# motherboard.net
KiCad netlist of a schematic drawn in EAGLE
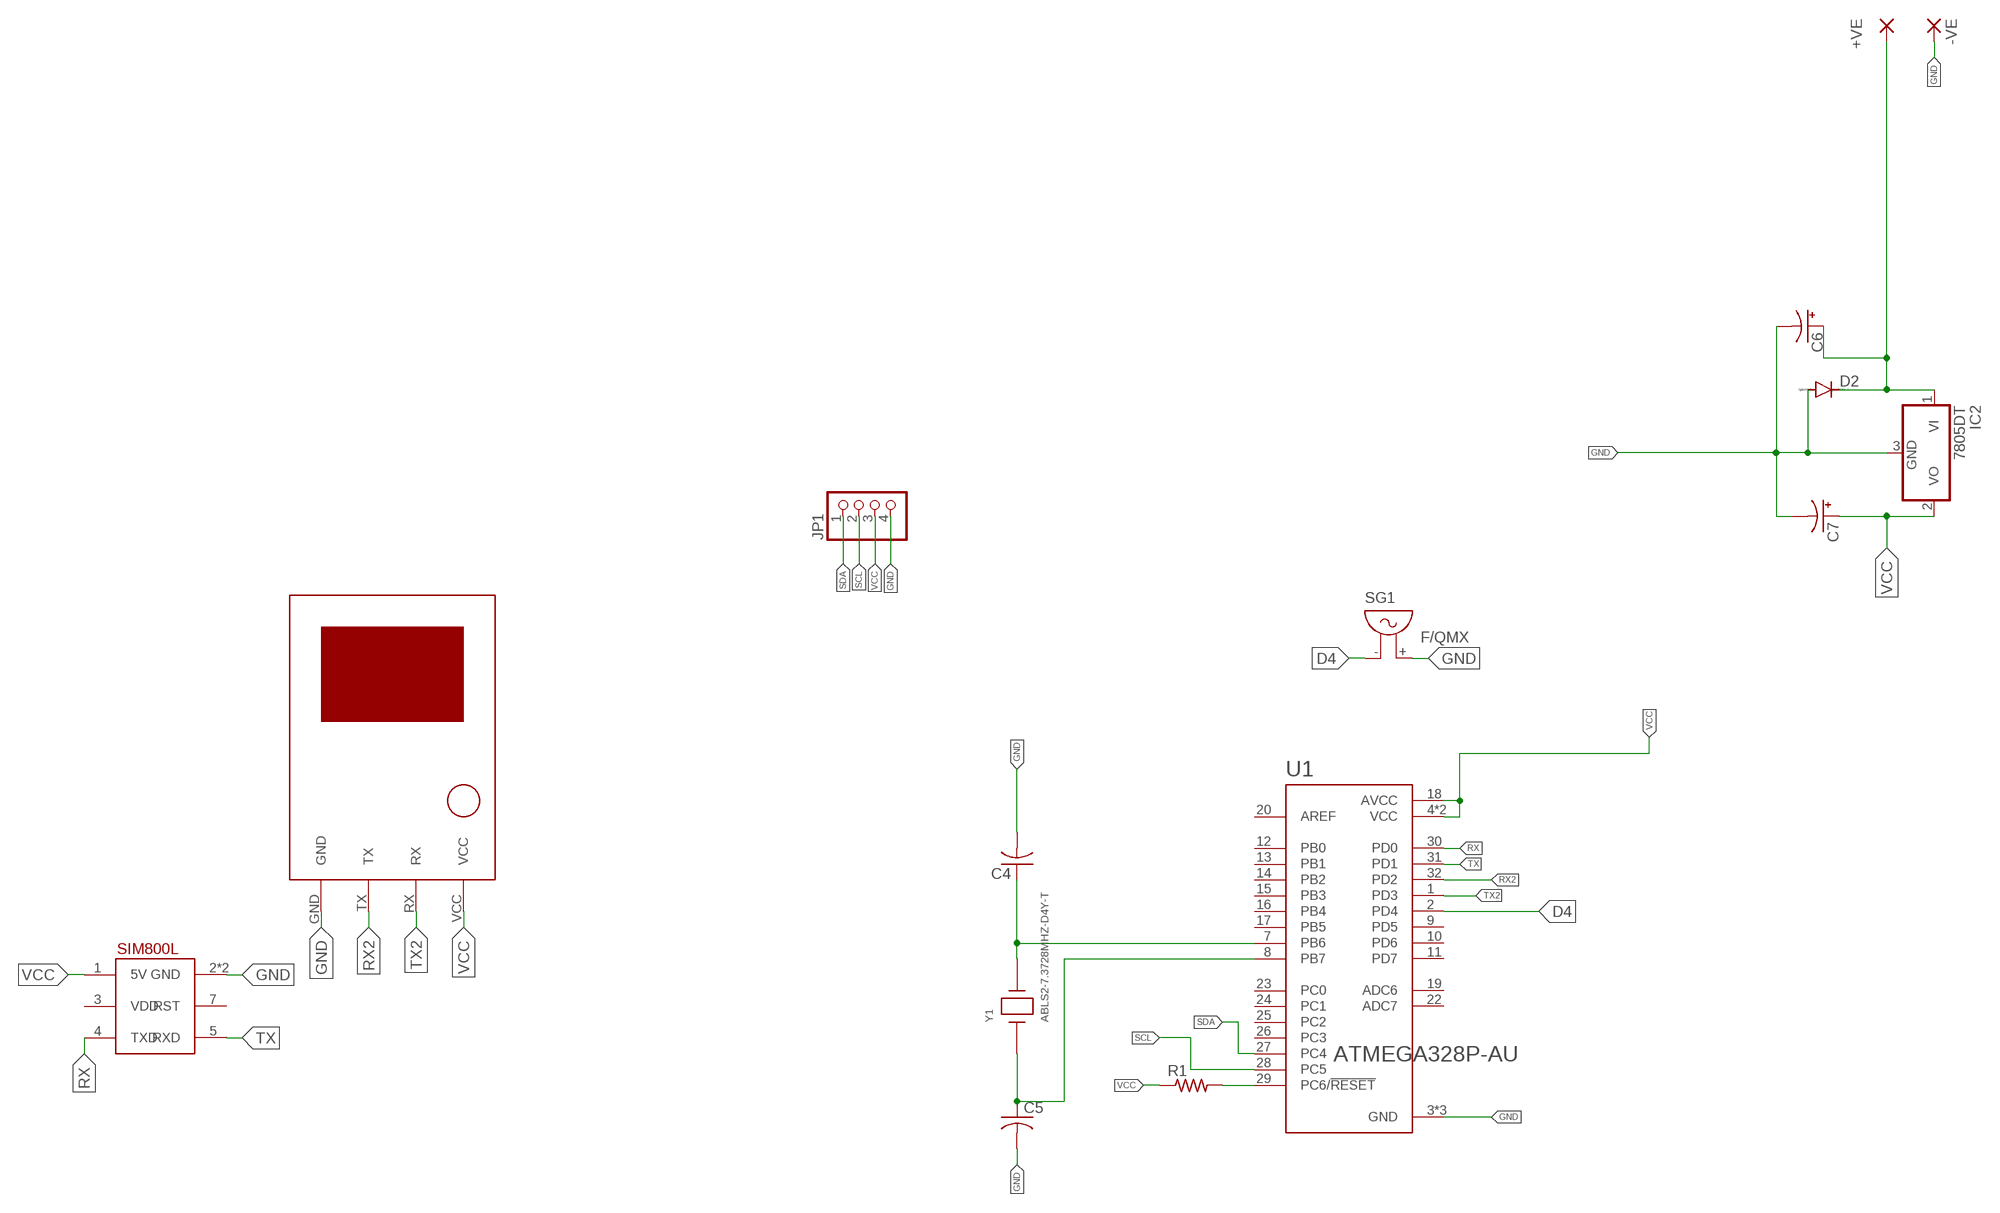
[diagram p0: schematic, sheet 1]

(export (version "E")
  (design (tool "Eeschema 10.0.6"))
  (components
    (comp (ref "+VE")
      (value "WIREPAD1,6/0,8")
      (footprint "eagle-import:1,6_0,8")
      (libsource (lib "eagle-import") (part "WIREPAD1,6/0,8"))
    )
    (comp (ref "-VE")
      (value "WIREPAD1,6/0,8")
      (footprint "eagle-import:1,6_0,8")
      (libsource (lib "eagle-import") (part "WIREPAD1,6/0,8"))
    )
    (comp (ref "C4")
      (value "C-US025-024X044")
      (footprint "eagle-import:C025-024X044")
      (libsource (lib "eagle-import") (part "C-US025-024X044"))
    )
    (comp (ref "C5")
      (value "C-US025-024X044")
      (footprint "eagle-import:C025-024X044")
      (libsource (lib "eagle-import") (part "C-US025-024X044"))
    )
    (comp (ref "C6")
      (value "CPOL-US153CLV-1010")
      (footprint "eagle-import:153CLV-1010")
      (libsource (lib "eagle-import") (part "CPOL-US153CLV-1010"))
    )
    (comp (ref "C7")
      (value "CPOL-US153CLV-1010")
      (footprint "eagle-import:153CLV-1010")
      (libsource (lib "eagle-import") (part "CPOL-US153CLV-1010"))
    )
    (comp (ref "D2")
      (value "DIODE-DO214AC")
      (footprint "eagle-import:DO214AC")
      (libsource (lib "eagle-import") (part "DIODE-DO214AC"))
    )
    (comp (ref "IC2")
      (value "7805DT")
      (footprint "eagle-import:TO252")
      (libsource (lib "eagle-import") (part "78DT05"))
    )
    (comp (ref "JP1")
      (value "PINHD-1X4")
      (footprint "eagle-import:1X04")
      (libsource (lib "eagle-import") (part "PINHD-1X4"))
    )
    (comp (ref "R1")
      (value "R-US_R0603")
      (footprint "eagle-import:R0603")
      (libsource (lib "eagle-import") (part "R-US_R0603"))
    )
    (comp (ref "SG1")
      (value "F/QMX")
      (footprint "eagle-import:F_QMX")
      (libsource (lib "eagle-import") (part "F/QMX"))
    )
    (comp (ref "U$1")
      (value "U-BLOX-NEO6V2")
      (footprint "eagle-import:U-BLOX-NEO6V2")
      (libsource (lib "eagle-import") (part "U-BLOX-NEO6V2"))
    )
    (comp (ref "U$2")
      (value "SIM800L")
      (footprint "eagle-import:SIP")
      (libsource (lib "eagle-import") (part "SIM800L"))
    )
    (comp (ref "U1")
      (value "ATMEGA328P-AU")
      (footprint "eagle-import:QFP80P900X900X120-32N")
      (fields (field (name "MF") "Microchip Technology"))
      (libsource (lib "eagle-import") (part "ATMEGA328P-AU"))
    )
    (comp (ref "Y1")
      (value "ABLS2-7.3728MHZ-D4Y-T")
      (footprint "eagle-import:XTAL_ABLS2-7.3728MHZ-D4Y-T")
      (fields (field (name "MF") "Abracon"))
      (libsource (lib "eagle-import") (part "ABLS2-7.3728MHZ-D4Y-T"))
    )
  )
  (nets
    (net (code "1") (name "D4") (class "Default")
      (node (ref "SG1") (pin "-") (pinfunction "1_-") (pintype "passive"))
      (node (ref "U1") (pin "2") (pinfunction "PD4_2") (pintype "bidirectional"))
    )
    (net (code "2") (name "GND") (class "Default")
      (node (ref "-VE") (pin "1") (pinfunction "P_1") (pintype "passive"))
      (node (ref "C4") (pin "2") (pinfunction "2_2") (pintype "passive"))
      (node (ref "C5") (pin "2") (pinfunction "2_2") (pintype "passive"))
      (node (ref "C6") (pin "-") (pinfunction "-_-") (pintype "passive"))
      (node (ref "C7") (pin "-") (pinfunction "-_-") (pintype "passive"))
      (node (ref "D2") (pin "A") (pinfunction "A_A") (pintype "passive"))
      (node (ref "IC2") (pin "3") (pinfunction "GND_3") (pintype "passive"))
      (node (ref "JP1") (pin "4") (pinfunction "4_4") (pintype "passive"))
      (node (ref "SG1") (pin "+") (pinfunction "2_+") (pintype "passive"))
      (node (ref "U$1") (pin "GND") (pinfunction "GND_GND") (pintype "bidirectional"))
      (node (ref "U$2") (pin "2") (pinfunction "GND_2") (pintype "bidirectional"))
      (node (ref "U$2") (pin "6") (pinfunction "GND_6") (pintype "bidirectional"))
      (node (ref "U1") (pin "21") (pinfunction "GND_21") (pintype "power_in"))
      (node (ref "U1") (pin "3") (pinfunction "GND_3") (pintype "power_in"))
      (node (ref "U1") (pin "5") (pinfunction "GND_5") (pintype "power_in"))
    )
    (net (code "3") (name "Net-(+VE-P)") (class "Default")
      (node (ref "+VE") (pin "1") (pinfunction "P_1") (pintype "passive"))
      (node (ref "C6") (pin "+") (pinfunction "+_+") (pintype "passive"))
      (node (ref "D2") (pin "C") (pinfunction "C_C") (pintype "passive"))
      (node (ref "IC2") (pin "1") (pinfunction "VI_1") (pintype "input"))
    )
    (net (code "4") (name "Net-(U1-PB6)") (class "Default")
      (node (ref "C4") (pin "1") (pinfunction "1_1") (pintype "passive"))
      (node (ref "U1") (pin "7") (pinfunction "PB6_7") (pintype "bidirectional"))
      (node (ref "Y1") (pin "2") (pinfunction "2_2") (pintype "passive"))
    )
    (net (code "5") (name "Net-(U1-PB7)") (class "Default")
      (node (ref "C5") (pin "1") (pinfunction "1_1") (pintype "passive"))
      (node (ref "U1") (pin "8") (pinfunction "PB7_8") (pintype "bidirectional"))
      (node (ref "Y1") (pin "1") (pinfunction "1_1") (pintype "passive"))
    )
    (net (code "6") (name "Net-(U1-PC6{slash}~{RESET})") (class "Default")
      (node (ref "R1") (pin "2") (pinfunction "2_2") (pintype "passive"))
      (node (ref "U1") (pin "29") (pinfunction "PC6/~{RESET}_29") (pintype "bidirectional"))
    )
    (net (code "7") (name "RX") (class "Default")
      (node (ref "U$2") (pin "4") (pinfunction "TXD_4") (pintype "bidirectional"))
      (node (ref "U1") (pin "30") (pinfunction "PD0_30") (pintype "bidirectional"))
    )
    (net (code "8") (name "RX2") (class "Default")
      (node (ref "U$1") (pin "TX") (pinfunction "TX_TX") (pintype "bidirectional"))
      (node (ref "U1") (pin "32") (pinfunction "PD2_32") (pintype "bidirectional"))
    )
    (net (code "9") (name "SCL") (class "Default")
      (node (ref "JP1") (pin "2") (pinfunction "2_2") (pintype "passive"))
      (node (ref "U1") (pin "28") (pinfunction "PC5_28") (pintype "bidirectional"))
    )
    (net (code "10") (name "SDA") (class "Default")
      (node (ref "JP1") (pin "1") (pinfunction "1_1") (pintype "passive"))
      (node (ref "U1") (pin "27") (pinfunction "PC4_27") (pintype "bidirectional"))
    )
    (net (code "11") (name "TX") (class "Default")
      (node (ref "U$2") (pin "5") (pinfunction "RXD_5") (pintype "bidirectional"))
      (node (ref "U1") (pin "31") (pinfunction "PD1_31") (pintype "bidirectional"))
    )
    (net (code "12") (name "TX2") (class "Default")
      (node (ref "U$1") (pin "RX") (pinfunction "RX_RX") (pintype "bidirectional"))
      (node (ref "U1") (pin "1") (pinfunction "PD3_1") (pintype "bidirectional"))
    )
    (net (code "13") (name "VCC") (class "Default")
      (node (ref "C7") (pin "+") (pinfunction "+_+") (pintype "passive"))
      (node (ref "IC2") (pin "2") (pinfunction "VO_2") (pintype "passive"))
      (node (ref "JP1") (pin "3") (pinfunction "3_3") (pintype "passive"))
      (node (ref "R1") (pin "1") (pinfunction "1_1") (pintype "passive"))
      (node (ref "U$1") (pin "VCC") (pinfunction "VCC_VCC") (pintype "bidirectional"))
      (node (ref "U$2") (pin "1") (pinfunction "5V_1") (pintype "bidirectional"))
      (node (ref "U1") (pin "18") (pinfunction "AVCC_18") (pintype "power_in"))
      (node (ref "U1") (pin "4") (pinfunction "VCC_4") (pintype "power_in"))
      (node (ref "U1") (pin "6") (pinfunction "VCC_6") (pintype "power_in"))
    )
    (net (code "14") (name "unconnected-(U$2-RST-Pad7)") (class "Default")
      (node (ref "U$2") (pin "7") (pinfunction "RST_7") (pintype "bidirectional"))
    )
    (net (code "15") (name "unconnected-(U$2-VDD-Pad3)") (class "Default")
      (node (ref "U$2") (pin "3") (pinfunction "VDD_3") (pintype "bidirectional"))
    )
    (net (code "16") (name "unconnected-(U1-ADC6-Pad19)") (class "Default")
      (node (ref "U1") (pin "19") (pinfunction "ADC6_19") (pintype "bidirectional"))
    )
    (net (code "17") (name "unconnected-(U1-ADC7-Pad22)") (class "Default")
      (node (ref "U1") (pin "22") (pinfunction "ADC7_22") (pintype "bidirectional"))
    )
    (net (code "18") (name "unconnected-(U1-AREF-Pad20)") (class "Default")
      (node (ref "U1") (pin "20") (pinfunction "AREF_20") (pintype "input"))
    )
    (net (code "19") (name "unconnected-(U1-PB0-Pad12)") (class "Default")
      (node (ref "U1") (pin "12") (pinfunction "PB0_12") (pintype "bidirectional"))
    )
    (net (code "20") (name "unconnected-(U1-PB1-Pad13)") (class "Default")
      (node (ref "U1") (pin "13") (pinfunction "PB1_13") (pintype "bidirectional"))
    )
    (net (code "21") (name "unconnected-(U1-PB2-Pad14)") (class "Default")
      (node (ref "U1") (pin "14") (pinfunction "PB2_14") (pintype "bidirectional"))
    )
    (net (code "22") (name "unconnected-(U1-PB3-Pad15)") (class "Default")
      (node (ref "U1") (pin "15") (pinfunction "PB3_15") (pintype "bidirectional"))
    )
    (net (code "23") (name "unconnected-(U1-PB4-Pad16)") (class "Default")
      (node (ref "U1") (pin "16") (pinfunction "PB4_16") (pintype "bidirectional"))
    )
    (net (code "24") (name "unconnected-(U1-PB5-Pad17)") (class "Default")
      (node (ref "U1") (pin "17") (pinfunction "PB5_17") (pintype "bidirectional"))
    )
    (net (code "25") (name "unconnected-(U1-PC0-Pad23)") (class "Default")
      (node (ref "U1") (pin "23") (pinfunction "PC0_23") (pintype "bidirectional"))
    )
    (net (code "26") (name "unconnected-(U1-PC1-Pad24)") (class "Default")
      (node (ref "U1") (pin "24") (pinfunction "PC1_24") (pintype "bidirectional"))
    )
    (net (code "27") (name "unconnected-(U1-PC2-Pad25)") (class "Default")
      (node (ref "U1") (pin "25") (pinfunction "PC2_25") (pintype "bidirectional"))
    )
    (net (code "28") (name "unconnected-(U1-PC3-Pad26)") (class "Default")
      (node (ref "U1") (pin "26") (pinfunction "PC3_26") (pintype "bidirectional"))
    )
    (net (code "29") (name "unconnected-(U1-PD5-Pad9)") (class "Default")
      (node (ref "U1") (pin "9") (pinfunction "PD5_9") (pintype "bidirectional"))
    )
    (net (code "30") (name "unconnected-(U1-PD6-Pad10)") (class "Default")
      (node (ref "U1") (pin "10") (pinfunction "PD6_10") (pintype "bidirectional"))
    )
    (net (code "31") (name "unconnected-(U1-PD7-Pad11)") (class "Default")
      (node (ref "U1") (pin "11") (pinfunction "PD7_11") (pintype "bidirectional"))
    )
  )
)
